# Riego_2_0_b.net
KiCad netlist of a schematic drawn in EasyEDA
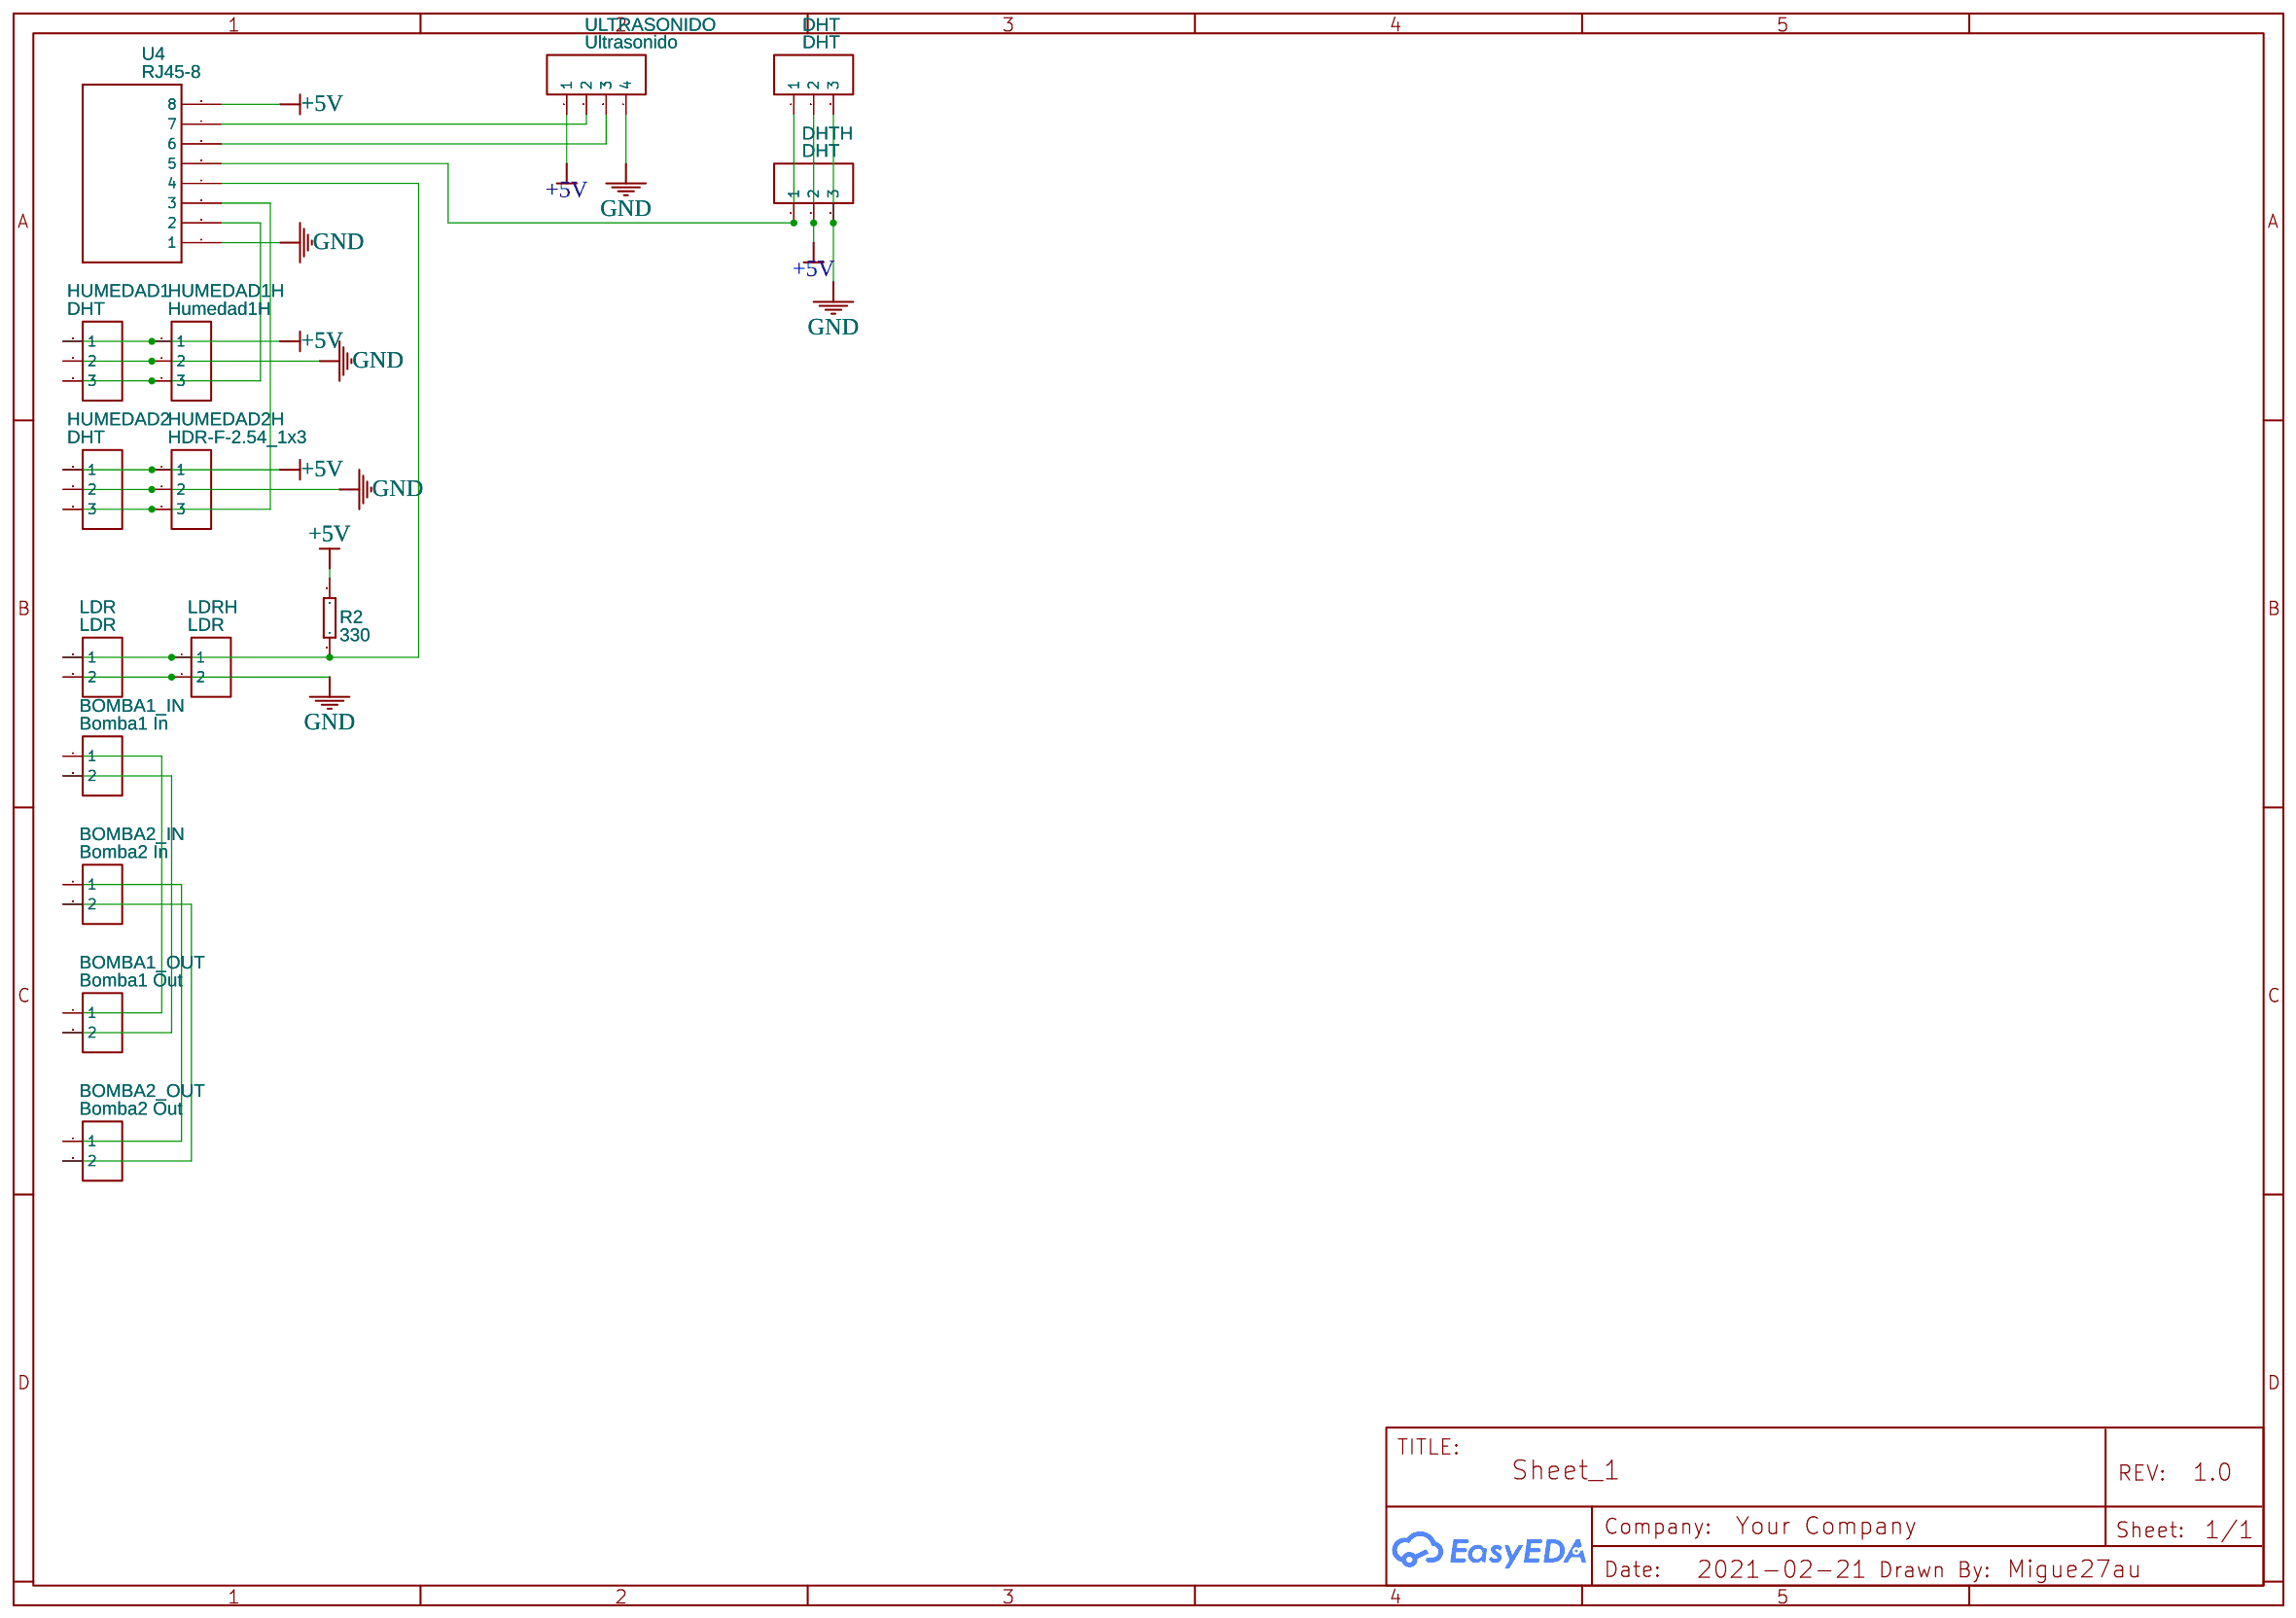
[diagram p0: schematic sheet]

(export (version "E")
  (design (tool "Eeschema 10.0.6"))
  (components
    (comp (ref "BOMBA1_IN") (value "Bomba1 In") (libsource (lib "") (part "CONN-TH_2P-P5.08_4")))
    (comp (ref "BOMBA1_OUT") (value "Bomba1 Out") (libsource (lib "") (part "CONN-TH_2P-P5.08_2")))
    (comp (ref "BOMBA2_IN") (value "Bomba2 In") (libsource (lib "") (part "CONN-TH_2P-P5.08_3")))
    (comp (ref "BOMBA2_OUT") (value "Bomba2 Out") (libsource (lib "") (part "CONN-TH_2P-P5.08_1")))
    (comp (ref "DHT") (value "DHT") (libsource (lib "") (part "CONN-TH_3P-P5.00_1")))
    (comp (ref "DHTH")
      (value "DHT")
      (fields (field (name "BOM_Supplier Part") "C146690"))
      (libsource (lib "") (part "HDR-F-2.54_1x3_2"))
    )
    (comp (ref "HUMEDAD1") (value "DHT") (libsource (lib "") (part "CONN-TH_3P-P5.00")))
    (comp (ref "HUMEDAD1H")
      (value "Humedad1H")
      (fields (field (name "BOM_Supplier Part") "C146690"))
      (libsource (lib "") (part "HDR-F-2.54_1x3_1"))
    )
    (comp (ref "HUMEDAD2") (value "DHT") (libsource (lib "") (part "CONN-TH_3P-P5.00")))
    (comp (ref "HUMEDAD2H")
      (value "HDR-F-2.54_1x3")
      (fields (field (name "BOM_Supplier Part") "C146690"))
      (libsource (lib "") (part "HDR-F-2.54_1x3"))
    )
    (comp (ref "LDR") (value "LDR") (libsource (lib "") (part "CONN-TH_2P-P5.08")))
    (comp (ref "LDRH")
      (value "LDR")
      (fields (field (name "BOM_Supplier Part") "C49661"))
      (libsource (lib "") (part "HDR-F-2.54_1x2"))
    )
    (comp (ref "R2") (value "330") (libsource (lib "") (part "RESISTOR")))
    (comp (ref "U4") (value "RJ45-8") (libsource (lib "") (part "RJ45-8")))
    (comp (ref "ULTRASONIDO")
      (value "Ultrasonido")
      (fields (field (name "BOM_Supplier Part") "C225501"))
      (libsource (lib "") (part "HDR-F-2.54_1x4"))
    )
  )
  (nets
    (net (code "1") (name "+5V") (class "Default")
      (node (ref "DHT") (pin "2") (pinfunction "2_2") (pintype "unspecified"))
      (node (ref "DHTH") (pin "2") (pinfunction "2_2") (pintype "input"))
      (node (ref "HUMEDAD1") (pin "1") (pinfunction "1_1") (pintype "unspecified"))
      (node (ref "HUMEDAD1H") (pin "1") (pinfunction "1_1") (pintype "input"))
      (node (ref "HUMEDAD2") (pin "1") (pinfunction "1_1") (pintype "unspecified"))
      (node (ref "HUMEDAD2H") (pin "1") (pinfunction "1_1") (pintype "input"))
      (node (ref "R2") (pin "2") (pinfunction "2_2") (pintype "unspecified"))
      (node (ref "U4") (pin "8") (pinfunction "8_8") (pintype "unspecified"))
      (node (ref "ULTRASONIDO") (pin "1") (pinfunction "1_1") (pintype "unspecified"))
    )
    (net (code "2") (name "GND") (class "Default")
      (node (ref "DHT") (pin "3") (pinfunction "3_3") (pintype "unspecified"))
      (node (ref "DHTH") (pin "3") (pinfunction "3_3") (pintype "input"))
      (node (ref "HUMEDAD1") (pin "2") (pinfunction "2_2") (pintype "unspecified"))
      (node (ref "HUMEDAD1H") (pin "2") (pinfunction "2_2") (pintype "input"))
      (node (ref "HUMEDAD2") (pin "2") (pinfunction "2_2") (pintype "unspecified"))
      (node (ref "HUMEDAD2H") (pin "2") (pinfunction "2_2") (pintype "input"))
      (node (ref "LDR") (pin "2") (pinfunction "2_2") (pintype "unspecified"))
      (node (ref "LDRH") (pin "2") (pinfunction "2_2") (pintype "input"))
      (node (ref "U4") (pin "1") (pinfunction "1_1") (pintype "unspecified"))
      (node (ref "ULTRASONIDO") (pin "4") (pinfunction "4_4") (pintype "unspecified"))
    )
    (net (code "3") (name "Net-(BOMBA1_IN-Pad1)") (class "Default")
      (node (ref "BOMBA1_IN") (pin "1") (pinfunction "1_1") (pintype "unspecified"))
      (node (ref "BOMBA1_OUT") (pin "1") (pinfunction "1_1") (pintype "unspecified"))
    )
    (net (code "4") (name "Net-(BOMBA1_IN-Pad2)") (class "Default")
      (node (ref "BOMBA1_IN") (pin "2") (pinfunction "2_2") (pintype "unspecified"))
      (node (ref "BOMBA1_OUT") (pin "2") (pinfunction "2_2") (pintype "unspecified"))
    )
    (net (code "5") (name "Net-(BOMBA2_IN-Pad1)") (class "Default")
      (node (ref "BOMBA2_IN") (pin "1") (pinfunction "1_1") (pintype "unspecified"))
      (node (ref "BOMBA2_OUT") (pin "1") (pinfunction "1_1") (pintype "unspecified"))
    )
    (net (code "6") (name "Net-(BOMBA2_IN-Pad2)") (class "Default")
      (node (ref "BOMBA2_IN") (pin "2") (pinfunction "2_2") (pintype "unspecified"))
      (node (ref "BOMBA2_OUT") (pin "2") (pinfunction "2_2") (pintype "unspecified"))
    )
    (net (code "7") (name "Net-(DHT-Pad1)") (class "Default")
      (node (ref "DHT") (pin "1") (pinfunction "1_1") (pintype "unspecified"))
      (node (ref "DHTH") (pin "1") (pinfunction "1_1") (pintype "input"))
      (node (ref "U4") (pin "5") (pinfunction "5_5") (pintype "unspecified"))
    )
    (net (code "8") (name "Net-(HUMEDAD1-Pad3)") (class "Default")
      (node (ref "HUMEDAD1") (pin "3") (pinfunction "3_3") (pintype "unspecified"))
      (node (ref "HUMEDAD1H") (pin "3") (pinfunction "3_3") (pintype "input"))
      (node (ref "U4") (pin "2") (pinfunction "2_2") (pintype "unspecified"))
    )
    (net (code "9") (name "Net-(HUMEDAD2-Pad3)") (class "Default")
      (node (ref "HUMEDAD2") (pin "3") (pinfunction "3_3") (pintype "unspecified"))
      (node (ref "HUMEDAD2H") (pin "3") (pinfunction "3_3") (pintype "input"))
      (node (ref "U4") (pin "3") (pinfunction "3_3") (pintype "unspecified"))
    )
    (net (code "10") (name "Net-(LDR-Pad1)") (class "Default")
      (node (ref "LDR") (pin "1") (pinfunction "1_1") (pintype "unspecified"))
      (node (ref "LDRH") (pin "1") (pinfunction "1_1") (pintype "input"))
      (node (ref "R2") (pin "1") (pinfunction "1_1") (pintype "unspecified"))
      (node (ref "U4") (pin "4") (pinfunction "4_4") (pintype "unspecified"))
    )
    (net (code "11") (name "Net-(U4-Pad6)") (class "Default")
      (node (ref "U4") (pin "6") (pinfunction "6_6") (pintype "unspecified"))
      (node (ref "ULTRASONIDO") (pin "3") (pinfunction "3_3") (pintype "unspecified"))
    )
    (net (code "12") (name "Net-(U4-Pad7)") (class "Default")
      (node (ref "U4") (pin "7") (pinfunction "7_7") (pintype "unspecified"))
      (node (ref "ULTRASONIDO") (pin "2") (pinfunction "2_2") (pintype "unspecified"))
    )
  )
)
